# VR_fille_alim_V1_0.net
KiCad netlist of a schematic drawn in EAGLE
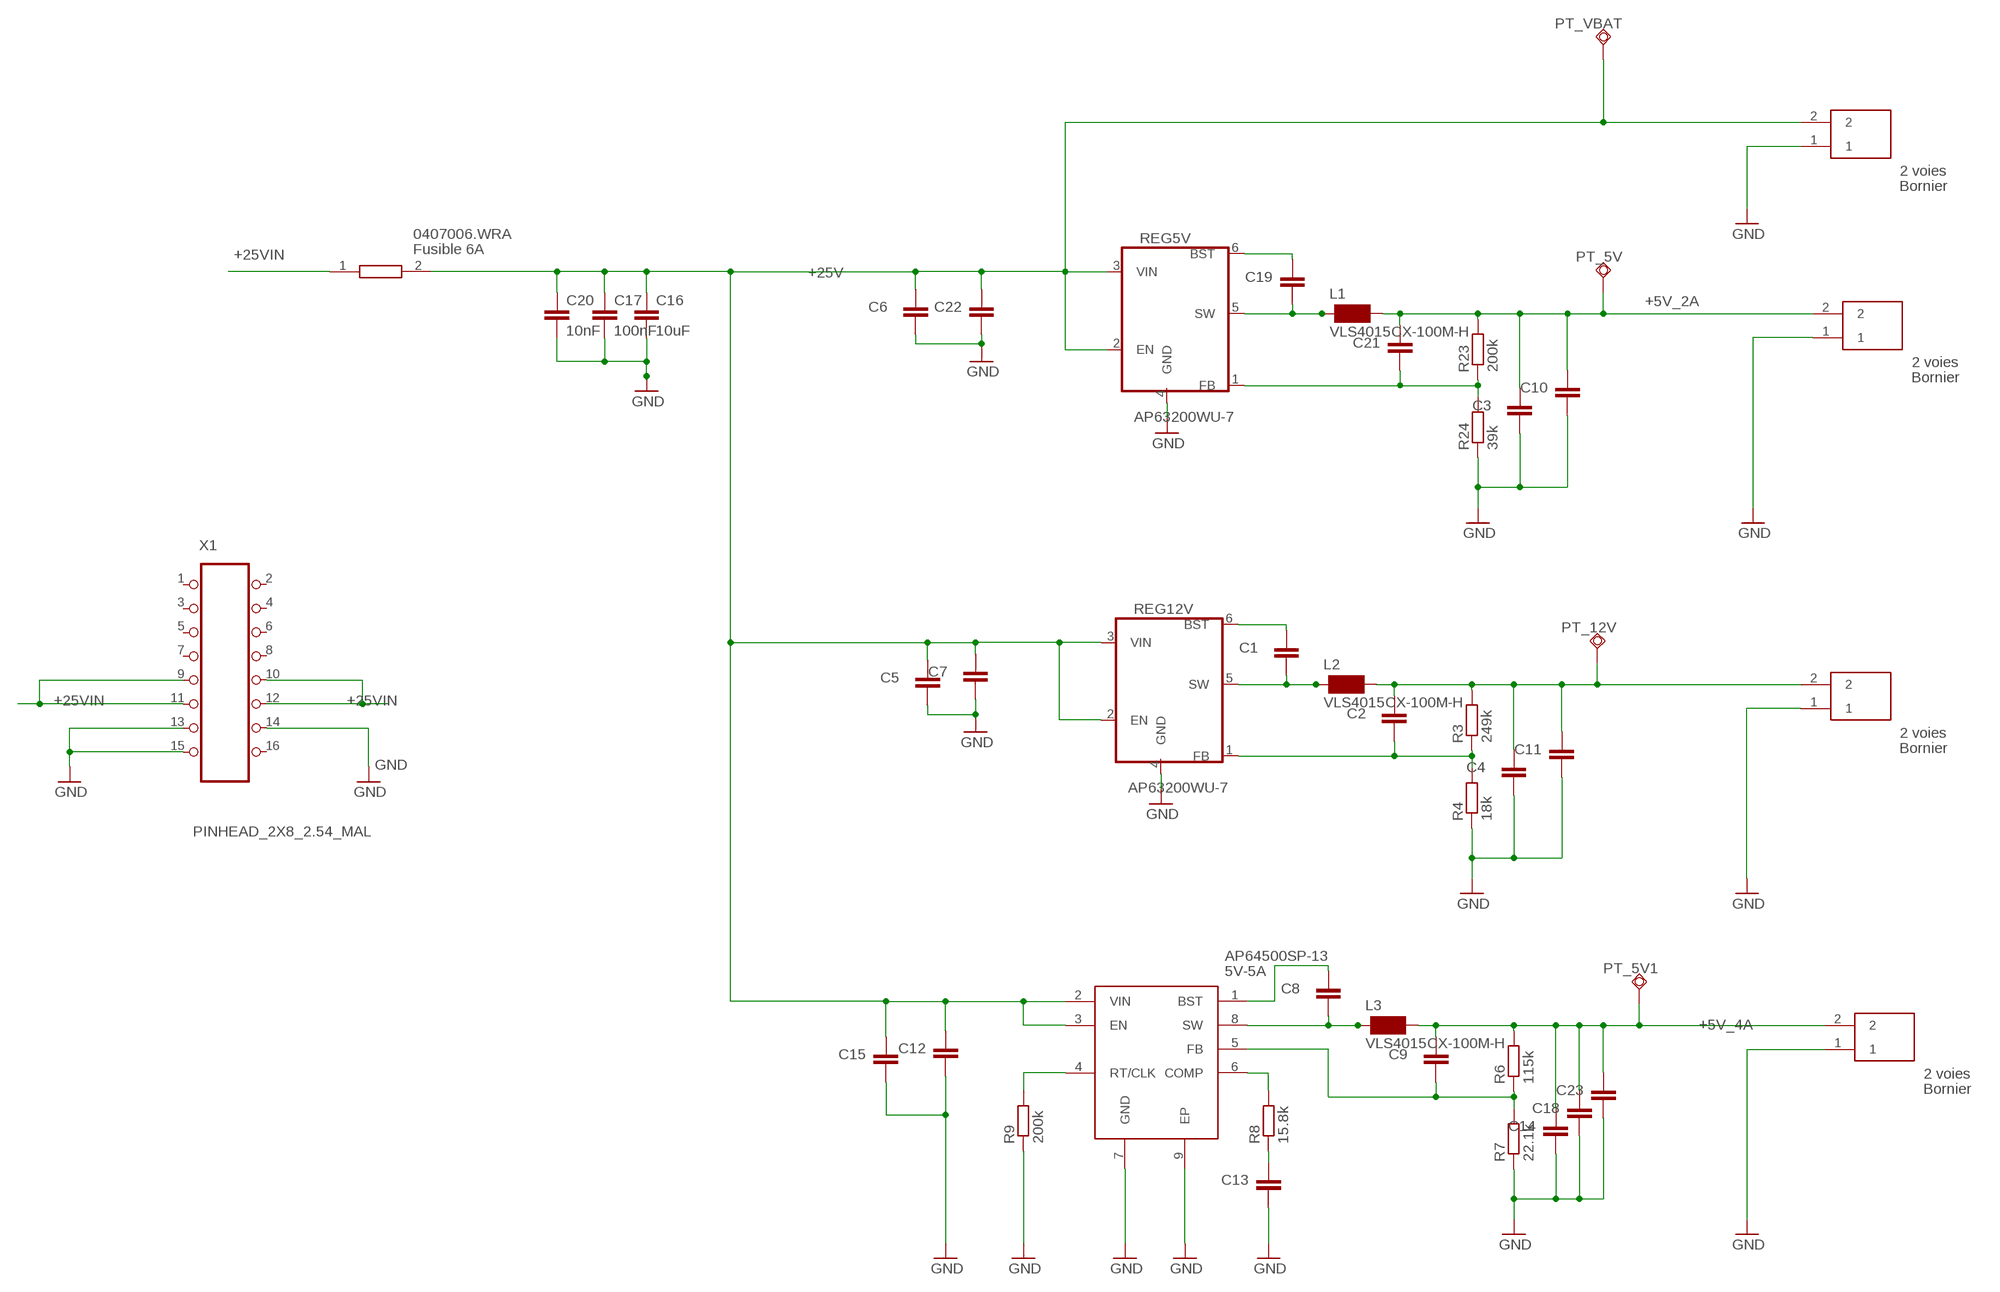
[diagram p0: schematic, sheet 1]

(export (version "E")
  (design (tool "Eeschema 10.0.6"))
  (components
    (comp (ref "C1")
      (value "100nF")
      (footprint "eagle-import:C0402")
      (libsource (lib "eagle-import") (part "C-EUC0402"))
    )
    (comp (ref "C2")
      (value "56pF")
      (footprint "eagle-import:C0402")
      (libsource (lib "eagle-import") (part "C-EUC0402"))
    )
    (comp (ref "C3")
      (value "22uF")
      (footprint "eagle-import:C0402")
      (libsource (lib "eagle-import") (part "C-EUC0402"))
    )
    (comp (ref "C4")
      (value "22uF")
      (footprint "eagle-import:C0402")
      (libsource (lib "eagle-import") (part "C-EUC0402"))
    )
    (comp (ref "C5")
      (value "100nF")
      (footprint "eagle-import:C0402")
      (libsource (lib "eagle-import") (part "C-EUC0402"))
    )
    (comp (ref "C6")
      (value "100nF")
      (footprint "eagle-import:C0402")
      (libsource (lib "eagle-import") (part "C-EUC0402"))
    )
    (comp (ref "C7")
      (value "10uF")
      (footprint "eagle-import:C0402")
      (libsource (lib "eagle-import") (part "C-EUC0402"))
    )
    (comp (ref "C8")
      (value "100nF")
      (footprint "eagle-import:C0402")
      (libsource (lib "eagle-import") (part "C-EUC0402"))
    )
    (comp (ref "C9")
      (value "100pF")
      (footprint "eagle-import:C0402")
      (libsource (lib "eagle-import") (part "C-EUC0402"))
    )
    (comp (ref "C10")
      (value "22uF")
      (footprint "eagle-import:C0402")
      (libsource (lib "eagle-import") (part "C-EUC0402"))
    )
    (comp (ref "C11")
      (value "22uF")
      (footprint "eagle-import:C0402")
      (libsource (lib "eagle-import") (part "C-EUC0402"))
    )
    (comp (ref "C12")
      (value "10uF")
      (footprint "eagle-import:C0402")
      (libsource (lib "eagle-import") (part "C-EUC0402"))
    )
    (comp (ref "C13")
      (value "2.7nF")
      (footprint "eagle-import:C0402")
      (libsource (lib "eagle-import") (part "C-EUC0402"))
    )
    (comp (ref "C14")
      (value "22uF")
      (footprint "eagle-import:C0402")
      (libsource (lib "eagle-import") (part "C-EUC0402"))
    )
    (comp (ref "C15")
      (value "100nF")
      (footprint "eagle-import:C0402")
      (libsource (lib "eagle-import") (part "C-EUC0402"))
    )
    (comp (ref "C16")
      (value "10uF")
      (footprint "eagle-import:C0805")
      (libsource (lib "eagle-import") (part "C-EUC0805"))
    )
    (comp (ref "C17")
      (value "100nF")
      (footprint "eagle-import:C0805")
      (libsource (lib "eagle-import") (part "C-EUC0805"))
    )
    (comp (ref "C18")
      (value "22uF")
      (footprint "eagle-import:C0402")
      (libsource (lib "eagle-import") (part "C-EUC0402"))
    )
    (comp (ref "C19")
      (value "100nF")
      (footprint "eagle-import:C0402")
      (libsource (lib "eagle-import") (part "C-EUC0402"))
    )
    (comp (ref "C20")
      (value "10nF")
      (footprint "eagle-import:C0805")
      (libsource (lib "eagle-import") (part "C-EUC0805"))
    )
    (comp (ref "C21")
      (value "100pF")
      (footprint "eagle-import:C0402")
      (libsource (lib "eagle-import") (part "C-EUC0402"))
    )
    (comp (ref "C22")
      (value "10uF")
      (footprint "eagle-import:C0402")
      (libsource (lib "eagle-import") (part "C-EUC0402"))
    )
    (comp (ref "C23")
      (value "22uF")
      (footprint "eagle-import:C0402")
      (libsource (lib "eagle-import") (part "C-EUC0402"))
    )
    (comp (ref "F1")
      (value "0407006.WRA")
      (footprint "eagle-import:FUSC3216X98N")
      (fields (field (name "MOUSER_PART_NUMBER") "576-0407006.WRA"))
      (libsource (lib "eagle-import") (part "0407006.WRA"))
    )
    (comp (ref "IC1")
      (value "AP64500SP-13")
      (footprint "eagle-import:SOIC127P600X163-9N")
      (fields (field (name "MOUSER_PART_NUMBER") "621-AP64500SP-13"))
      (libsource (lib "eagle-import") (part "AP64500SP-13"))
    )
    (comp (ref "J1")
      (value "691214110002")
      (footprint "eagle-import:691214110002")
      (fields (field (name "MOUSER_PART_NUMBER") "710-691214110002"))
      (libsource (lib "eagle-import") (part "691214110002"))
    )
    (comp (ref "J2")
      (value "691214110002")
      (footprint "eagle-import:691214110002")
      (fields (field (name "MOUSER_PART_NUMBER") "710-691214110002"))
      (libsource (lib "eagle-import") (part "691214110002"))
    )
    (comp (ref "J3")
      (value "691214110002")
      (footprint "eagle-import:691214110002")
      (fields (field (name "MOUSER_PART_NUMBER") "710-691214110002"))
      (libsource (lib "eagle-import") (part "691214110002"))
    )
    (comp (ref "J5")
      (value "691214110002")
      (footprint "eagle-import:691214110002")
      (fields (field (name "MOUSER_PART_NUMBER") "710-691214110002"))
      (libsource (lib "eagle-import") (part "691214110002"))
    )
    (comp (ref "L1")
      (value "VLS4015CX-100M-H")
      (footprint "eagle-import:VLS4015")
      (libsource (lib "eagle-import") (part "VLS4015"))
    )
    (comp (ref "L2")
      (value "VLS4015CX-100M-H")
      (footprint "eagle-import:VLS4015")
      (libsource (lib "eagle-import") (part "VLS4015"))
    )
    (comp (ref "L3")
      (value "VLS4015CX-100M-H")
      (footprint "eagle-import:VLS4015")
      (libsource (lib "eagle-import") (part "VLS4015"))
    )
    (comp (ref "PT_5V")
      (value "POINT_TEST")
      (footprint "eagle-import:POINT_TEST")
      (libsource (lib "eagle-import") (part "POINT_TEST"))
    )
    (comp (ref "PT_5V1")
      (value "POINT_TEST")
      (footprint "eagle-import:POINT_TEST")
      (libsource (lib "eagle-import") (part "POINT_TEST"))
    )
    (comp (ref "PT_12V")
      (value "POINT_TEST")
      (footprint "eagle-import:POINT_TEST")
      (libsource (lib "eagle-import") (part "POINT_TEST"))
    )
    (comp (ref "PT_VBAT")
      (value "POINT_TEST")
      (footprint "eagle-import:POINT_TEST")
      (libsource (lib "eagle-import") (part "POINT_TEST"))
    )
    (comp (ref "R3")
      (value "249k")
      (footprint "eagle-import:R0402")
      (libsource (lib "eagle-import") (part "R-EU_R0402"))
    )
    (comp (ref "R4")
      (value "18k")
      (footprint "eagle-import:R0402")
      (libsource (lib "eagle-import") (part "R-EU_R0402"))
    )
    (comp (ref "R6")
      (value "115k")
      (footprint "eagle-import:R0402")
      (libsource (lib "eagle-import") (part "R-EU_R0402"))
    )
    (comp (ref "R7")
      (value "22.1k")
      (footprint "eagle-import:R0402")
      (libsource (lib "eagle-import") (part "R-EU_R0402"))
    )
    (comp (ref "R8")
      (value "15.8k")
      (footprint "eagle-import:R0402")
      (libsource (lib "eagle-import") (part "R-EU_R0402"))
    )
    (comp (ref "R9")
      (value "200k")
      (footprint "eagle-import:R0402")
      (libsource (lib "eagle-import") (part "R-EU_R0402"))
    )
    (comp (ref "R23")
      (value "200k")
      (footprint "eagle-import:R0402")
      (libsource (lib "eagle-import") (part "R-EU_R0402"))
    )
    (comp (ref "R24")
      (value "39k")
      (footprint "eagle-import:R0402")
      (libsource (lib "eagle-import") (part "R-EU_R0402"))
    )
    (comp (ref "REG5V")
      (value "AP63200WU-7")
      (footprint "eagle-import:TSOT26")
      (libsource (lib "eagle-import") (part "AP6320X"))
    )
    (comp (ref "REG12V")
      (value "AP63200WU-7")
      (footprint "eagle-import:TSOT26")
      (libsource (lib "eagle-import") (part "AP6320X"))
    )
    (comp (ref "X1")
      (value "PINHEAD_2X8_2.54_MAL")
      (footprint "eagle-import:PINHEAD_2X8_2.54_MAL")
      (libsource (lib "eagle-import") (part "PINHEAD_2X8_2.54_MAL"))
    )
  )
  (nets
    (net (code "1") (name "/+5V_2A") (class "Default")
      (node (ref "C10") (pin "2") (pinfunction "2_2") (pintype "passive"))
      (node (ref "C21") (pin "2") (pinfunction "2_2") (pintype "passive"))
      (node (ref "C3") (pin "2") (pinfunction "2_2") (pintype "passive"))
      (node (ref "J1") (pin "2") (pinfunction "2_2") (pintype "bidirectional"))
      (node (ref "L1") (pin "2") (pinfunction "2_2") (pintype "passive"))
      (node (ref "PT_5V") (pin ">NAME") (pinfunction "TP_>NAME") (pintype "input"))
      (node (ref "R23") (pin "2") (pinfunction "2_2") (pintype "passive"))
    )
    (net (code "2") (name "/+5V_4A") (class "Default")
      (node (ref "C14") (pin "2") (pinfunction "2_2") (pintype "passive"))
      (node (ref "C18") (pin "2") (pinfunction "2_2") (pintype "passive"))
      (node (ref "C23") (pin "2") (pinfunction "2_2") (pintype "passive"))
      (node (ref "C9") (pin "2") (pinfunction "2_2") (pintype "passive"))
      (node (ref "J3") (pin "2") (pinfunction "2_2") (pintype "bidirectional"))
      (node (ref "L3") (pin "2") (pinfunction "2_2") (pintype "passive"))
      (node (ref "PT_5V1") (pin ">NAME") (pinfunction "TP_>NAME") (pintype "input"))
      (node (ref "R6") (pin "2") (pinfunction "2_2") (pintype "passive"))
    )
    (net (code "3") (name "/+25V") (class "Default")
      (node (ref "C12") (pin "2") (pinfunction "2_2") (pintype "passive"))
      (node (ref "C15") (pin "2") (pinfunction "2_2") (pintype "passive"))
      (node (ref "C16") (pin "1") (pinfunction "1_1") (pintype "passive"))
      (node (ref "C17") (pin "1") (pinfunction "1_1") (pintype "passive"))
      (node (ref "C20") (pin "1") (pinfunction "1_1") (pintype "passive"))
      (node (ref "C22") (pin "2") (pinfunction "2_2") (pintype "passive"))
      (node (ref "C5") (pin "2") (pinfunction "2_2") (pintype "passive"))
      (node (ref "C6") (pin "2") (pinfunction "2_2") (pintype "passive"))
      (node (ref "C7") (pin "2") (pinfunction "2_2") (pintype "passive"))
      (node (ref "F1") (pin "2") (pinfunction "2_2") (pintype "bidirectional"))
      (node (ref "IC1") (pin "2") (pinfunction "VIN_2") (pintype "bidirectional"))
      (node (ref "IC1") (pin "3") (pinfunction "EN_3") (pintype "bidirectional"))
      (node (ref "J5") (pin "2") (pinfunction "2_2") (pintype "bidirectional"))
      (node (ref "PT_VBAT") (pin ">NAME") (pinfunction "TP_>NAME") (pintype "input"))
      (node (ref "REG12V") (pin "2") (pinfunction "EN_2") (pintype "passive"))
      (node (ref "REG12V") (pin "3") (pinfunction "VIN_3") (pintype "passive"))
      (node (ref "REG5V") (pin "2") (pinfunction "EN_2") (pintype "passive"))
      (node (ref "REG5V") (pin "3") (pinfunction "VIN_3") (pintype "passive"))
    )
    (net (code "4") (name "/+25VIN") (class "Default")
      (node (ref "F1") (pin "1") (pinfunction "1_1") (pintype "bidirectional"))
      (node (ref "X1") (pin "10") (pinfunction "10_10") (pintype "passive"))
      (node (ref "X1") (pin "11") (pinfunction "11_11") (pintype "passive"))
      (node (ref "X1") (pin "12") (pinfunction "12_12") (pintype "passive"))
      (node (ref "X1") (pin "9") (pinfunction "9_9") (pintype "passive"))
    )
    (net (code "5") (name "GND") (class "Default")
      (node (ref "C10") (pin "1") (pinfunction "1_1") (pintype "passive"))
      (node (ref "C11") (pin "1") (pinfunction "1_1") (pintype "passive"))
      (node (ref "C12") (pin "1") (pinfunction "1_1") (pintype "passive"))
      (node (ref "C13") (pin "1") (pinfunction "1_1") (pintype "passive"))
      (node (ref "C14") (pin "1") (pinfunction "1_1") (pintype "passive"))
      (node (ref "C15") (pin "1") (pinfunction "1_1") (pintype "passive"))
      (node (ref "C16") (pin "2") (pinfunction "2_2") (pintype "passive"))
      (node (ref "C17") (pin "2") (pinfunction "2_2") (pintype "passive"))
      (node (ref "C18") (pin "1") (pinfunction "1_1") (pintype "passive"))
      (node (ref "C20") (pin "2") (pinfunction "2_2") (pintype "passive"))
      (node (ref "C22") (pin "1") (pinfunction "1_1") (pintype "passive"))
      (node (ref "C23") (pin "1") (pinfunction "1_1") (pintype "passive"))
      (node (ref "C3") (pin "1") (pinfunction "1_1") (pintype "passive"))
      (node (ref "C4") (pin "1") (pinfunction "1_1") (pintype "passive"))
      (node (ref "C5") (pin "1") (pinfunction "1_1") (pintype "passive"))
      (node (ref "C6") (pin "1") (pinfunction "1_1") (pintype "passive"))
      (node (ref "C7") (pin "1") (pinfunction "1_1") (pintype "passive"))
      (node (ref "IC1") (pin "7") (pinfunction "GND_7") (pintype "bidirectional"))
      (node (ref "IC1") (pin "9") (pinfunction "EP_9") (pintype "bidirectional"))
      (node (ref "J1") (pin "1") (pinfunction "1_1") (pintype "bidirectional"))
      (node (ref "J2") (pin "1") (pinfunction "1_1") (pintype "bidirectional"))
      (node (ref "J3") (pin "1") (pinfunction "1_1") (pintype "bidirectional"))
      (node (ref "J5") (pin "1") (pinfunction "1_1") (pintype "bidirectional"))
      (node (ref "R24") (pin "1") (pinfunction "1_1") (pintype "passive"))
      (node (ref "R4") (pin "1") (pinfunction "1_1") (pintype "passive"))
      (node (ref "R7") (pin "1") (pinfunction "1_1") (pintype "passive"))
      (node (ref "R9") (pin "1") (pinfunction "1_1") (pintype "passive"))
      (node (ref "REG12V") (pin "4") (pinfunction "GND_4") (pintype "passive"))
      (node (ref "REG5V") (pin "4") (pinfunction "GND_4") (pintype "passive"))
      (node (ref "X1") (pin "13") (pinfunction "13_13") (pintype "passive"))
      (node (ref "X1") (pin "14") (pinfunction "14_14") (pintype "passive"))
      (node (ref "X1") (pin "15") (pinfunction "15_15") (pintype "passive"))
    )
    (net (code "6") (name "Net-(C13-Pad2)") (class "Default")
      (node (ref "C13") (pin "2") (pinfunction "2_2") (pintype "passive"))
      (node (ref "R8") (pin "1") (pinfunction "1_1") (pintype "passive"))
    )
    (net (code "7") (name "Net-(IC1-BST)") (class "Default")
      (node (ref "C8") (pin "2") (pinfunction "2_2") (pintype "passive"))
      (node (ref "IC1") (pin "1") (pinfunction "BST_1") (pintype "bidirectional"))
    )
    (net (code "8") (name "Net-(IC1-COMP)") (class "Default")
      (node (ref "IC1") (pin "6") (pinfunction "COMP_6") (pintype "bidirectional"))
      (node (ref "R8") (pin "2") (pinfunction "2_2") (pintype "passive"))
    )
    (net (code "9") (name "Net-(IC1-FB)") (class "Default")
      (node (ref "C9") (pin "1") (pinfunction "1_1") (pintype "passive"))
      (node (ref "IC1") (pin "5") (pinfunction "FB_5") (pintype "bidirectional"))
      (node (ref "R6") (pin "1") (pinfunction "1_1") (pintype "passive"))
      (node (ref "R7") (pin "2") (pinfunction "2_2") (pintype "passive"))
    )
    (net (code "10") (name "Net-(IC1-RT{slash}CLK)") (class "Default")
      (node (ref "IC1") (pin "4") (pinfunction "RT/CLK_4") (pintype "bidirectional"))
      (node (ref "R9") (pin "2") (pinfunction "2_2") (pintype "passive"))
    )
    (net (code "11") (name "Net-(IC1-SW)") (class "Default")
      (node (ref "C8") (pin "1") (pinfunction "1_1") (pintype "passive"))
      (node (ref "IC1") (pin "8") (pinfunction "SW_8") (pintype "bidirectional"))
      (node (ref "L3") (pin "1") (pinfunction "1_1") (pintype "passive"))
    )
    (net (code "12") (name "Net-(PT_12V-TP)") (class "Default")
      (node (ref "C11") (pin "2") (pinfunction "2_2") (pintype "passive"))
      (node (ref "C2") (pin "2") (pinfunction "2_2") (pintype "passive"))
      (node (ref "C4") (pin "2") (pinfunction "2_2") (pintype "passive"))
      (node (ref "J2") (pin "2") (pinfunction "2_2") (pintype "bidirectional"))
      (node (ref "L2") (pin "2") (pinfunction "2_2") (pintype "passive"))
      (node (ref "PT_12V") (pin ">NAME") (pinfunction "TP_>NAME") (pintype "input"))
      (node (ref "R3") (pin "2") (pinfunction "2_2") (pintype "passive"))
    )
    (net (code "13") (name "Net-(REG5V-BST)") (class "Default")
      (node (ref "C19") (pin "2") (pinfunction "2_2") (pintype "passive"))
      (node (ref "REG5V") (pin "6") (pinfunction "BST_6") (pintype "passive"))
    )
    (net (code "14") (name "Net-(REG5V-FB)") (class "Default")
      (node (ref "C21") (pin "1") (pinfunction "1_1") (pintype "passive"))
      (node (ref "R23") (pin "1") (pinfunction "1_1") (pintype "passive"))
      (node (ref "R24") (pin "2") (pinfunction "2_2") (pintype "passive"))
      (node (ref "REG5V") (pin "1") (pinfunction "FB_1") (pintype "passive"))
    )
    (net (code "15") (name "Net-(REG5V-SW)") (class "Default")
      (node (ref "C19") (pin "1") (pinfunction "1_1") (pintype "passive"))
      (node (ref "L1") (pin "1") (pinfunction "1_1") (pintype "passive"))
      (node (ref "REG5V") (pin "5") (pinfunction "SW_5") (pintype "passive"))
    )
    (net (code "16") (name "Net-(REG12V-BST)") (class "Default")
      (node (ref "C1") (pin "2") (pinfunction "2_2") (pintype "passive"))
      (node (ref "REG12V") (pin "6") (pinfunction "BST_6") (pintype "passive"))
    )
    (net (code "17") (name "Net-(REG12V-FB)") (class "Default")
      (node (ref "C2") (pin "1") (pinfunction "1_1") (pintype "passive"))
      (node (ref "R3") (pin "1") (pinfunction "1_1") (pintype "passive"))
      (node (ref "R4") (pin "2") (pinfunction "2_2") (pintype "passive"))
      (node (ref "REG12V") (pin "1") (pinfunction "FB_1") (pintype "passive"))
    )
    (net (code "18") (name "Net-(REG12V-SW)") (class "Default")
      (node (ref "C1") (pin "1") (pinfunction "1_1") (pintype "passive"))
      (node (ref "L2") (pin "1") (pinfunction "1_1") (pintype "passive"))
      (node (ref "REG12V") (pin "5") (pinfunction "SW_5") (pintype "passive"))
    )
    (net (code "19") (name "unconnected-(X1-Pad1)") (class "Default")
      (node (ref "X1") (pin "1") (pinfunction "1_1") (pintype "passive"))
    )
    (net (code "20") (name "unconnected-(X1-Pad2)") (class "Default")
      (node (ref "X1") (pin "2") (pinfunction "2_2") (pintype "passive"))
    )
    (net (code "21") (name "unconnected-(X1-Pad3)") (class "Default")
      (node (ref "X1") (pin "3") (pinfunction "3_3") (pintype "passive"))
    )
    (net (code "22") (name "unconnected-(X1-Pad4)") (class "Default")
      (node (ref "X1") (pin "4") (pinfunction "4_4") (pintype "passive"))
    )
    (net (code "23") (name "unconnected-(X1-Pad5)") (class "Default")
      (node (ref "X1") (pin "5") (pinfunction "5_5") (pintype "passive"))
    )
    (net (code "24") (name "unconnected-(X1-Pad6)") (class "Default")
      (node (ref "X1") (pin "6") (pinfunction "6_6") (pintype "passive"))
    )
    (net (code "25") (name "unconnected-(X1-Pad7)") (class "Default")
      (node (ref "X1") (pin "7") (pinfunction "7_7") (pintype "passive"))
    )
    (net (code "26") (name "unconnected-(X1-Pad8)") (class "Default")
      (node (ref "X1") (pin "8") (pinfunction "8_8") (pintype "passive"))
    )
    (net (code "27") (name "unconnected-(X1-Pad16)") (class "Default")
      (node (ref "X1") (pin "16") (pinfunction "16_16") (pintype "passive"))
    )
  )
)
